# CellVoltageControl.net
KiCad netlist of a schematic drawn in Altium Designer
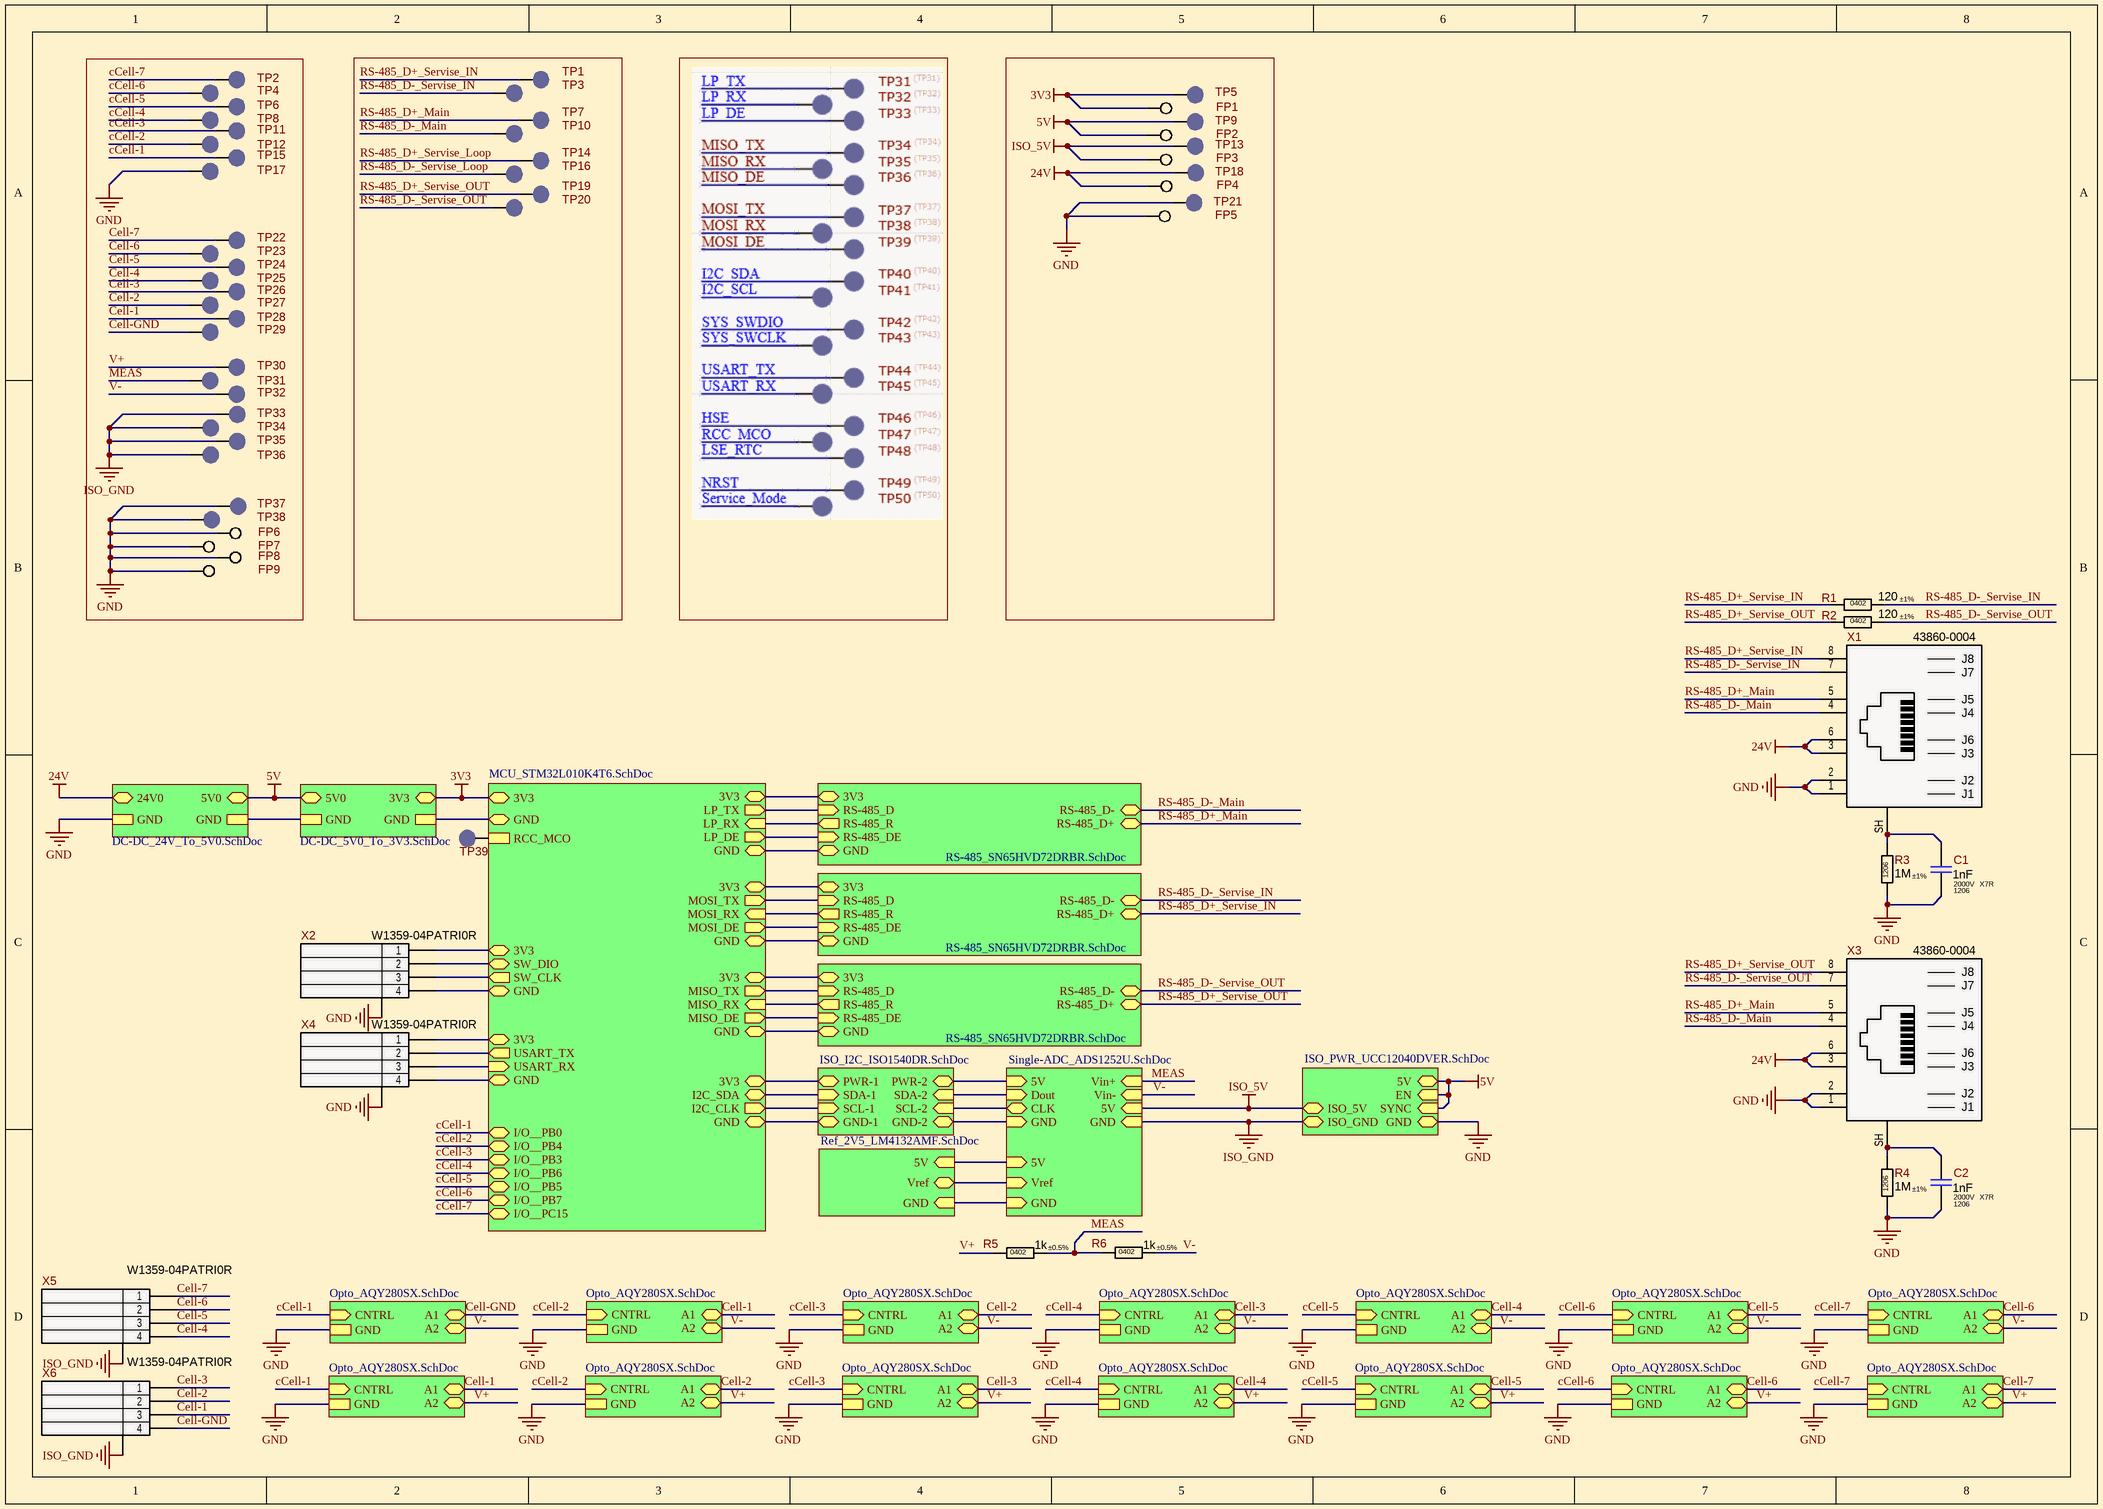
[diagram p0: CellVoltageControl.SchDoc]

(export (version "E")
  (design (tool "Eeschema 10.0.6"))
  (components
    (comp (ref "C1")
      (value "1nF")
      (footprint "CAP-1206(3216)X125T20")
      (description "1nF 2000V X7R ±10% 1206 Ceramic Capacitor RoHS")
      (fields
        (field (name "PACKAGE") "1206")
        (field (name "VOLTAGE") "2000V")
        (field (name "DIELECTRIC TYPE") "X7R")
        (field (name "PART NUMBER") "CC1206KKX7RDBB102")
        (field (name "MANUFACTURER") "Yageo")
      )
      (libsource (lib "EL.CVCM.T01") (part "Capacitor-NonPolar"))
    )
    (comp (ref "C2")
      (value "1nF")
      (footprint "CAP-1206(3216)X125T20")
      (description "1nF 2000V X7R ±10% 1206 Ceramic Capacitor RoHS")
      (fields
        (field (name "PACKAGE") "1206")
        (field (name "VOLTAGE") "2000V")
        (field (name "DIELECTRIC TYPE") "X7R")
        (field (name "PART NUMBER") "CC1206KKX7RDBB102")
        (field (name "MANUFACTURER") "Yageo")
      )
      (libsource (lib "EL.CVCM.T01") (part "Capacitor-NonPolar"))
    )
    (comp (ref "FP1")
      (value "PAD-1.1mm")
      (footprint "PAD-1.1mm")
      (description "1.1mm Pad for Plug-In or Receptacle")
      (fields (field (name "MANUFACTURER") "NONE"))
      (libsource (lib "EL.CVCM.T01") (part "Pad"))
    )
    (comp (ref "FP2")
      (value "PAD-1.1mm")
      (footprint "PAD-1.1mm")
      (description "1.1mm Pad for Plug-In or Receptacle")
      (fields (field (name "MANUFACTURER") "NONE"))
      (libsource (lib "EL.CVCM.T01") (part "Pad"))
    )
    (comp (ref "FP3")
      (value "PAD-1.1mm")
      (footprint "PAD-1.1mm")
      (description "1.1mm Pad for Plug-In or Receptacle")
      (fields (field (name "MANUFACTURER") "NONE"))
      (libsource (lib "EL.CVCM.T01") (part "Pad"))
    )
    (comp (ref "FP4")
      (value "PAD-1.1mm")
      (footprint "PAD-1.1mm")
      (description "1.1mm Pad for Plug-In or Receptacle")
      (fields (field (name "MANUFACTURER") "NONE"))
      (libsource (lib "EL.CVCM.T01") (part "Pad"))
    )
    (comp (ref "FP5")
      (value "PAD-1.1mm")
      (footprint "PAD-1.1mm")
      (description "1.1mm Pad for Plug-In or Receptacle")
      (fields (field (name "MANUFACTURER") "NONE"))
      (libsource (lib "EL.CVCM.T01") (part "Pad"))
    )
    (comp (ref "FP6")
      (value "PAD-1.1mm")
      (footprint "PAD-1.1mm")
      (description "1.1mm Pad for Plug-In or Receptacle")
      (fields (field (name "MANUFACTURER") "NONE"))
      (libsource (lib "EL.CVCM.T01") (part "Pad"))
    )
    (comp (ref "FP7")
      (value "PAD-1.1mm")
      (footprint "PAD-1.1mm")
      (description "1.1mm Pad for Plug-In or Receptacle")
      (fields (field (name "MANUFACTURER") "NONE"))
      (libsource (lib "EL.CVCM.T01") (part "Pad"))
    )
    (comp (ref "FP8")
      (value "PAD-1.1mm")
      (footprint "PAD-1.1mm")
      (description "1.1mm Pad for Plug-In or Receptacle")
      (fields (field (name "MANUFACTURER") "NONE"))
      (libsource (lib "EL.CVCM.T01") (part "Pad"))
    )
    (comp (ref "FP9")
      (value "PAD-1.1mm")
      (footprint "PAD-1.1mm")
      (description "1.1mm Pad for Plug-In or Receptacle")
      (fields (field (name "MANUFACTURER") "NONE"))
      (libsource (lib "EL.CVCM.T01") (part "Pad"))
    )
    (comp (ref "R1")
      (value "120")
      (footprint "R_ANY_CHIP_0402_HI")
      (description "120 Ohms ±1% 1/16W 0402 Thick Film Resistor")
      (fields
        (field (name "TOLERANCE") "±1%")
        (field (name "PACKAGE") "0402")
        (field (name "PART NUMBER") "RC0402FR-07120RL")
        (field (name "MANUFACTURER") "Yageo")
      )
      (libsource (lib "EL.CVCM.T01") (part "Resistor"))
    )
    (comp (ref "R2")
      (value "120")
      (footprint "R_ANY_CHIP_0402_HI")
      (description "120 Ohms ±1% 1/16W 0402 Thick Film Resistor")
      (fields
        (field (name "TOLERANCE") "±1%")
        (field (name "PACKAGE") "0402")
        (field (name "PART NUMBER") "RC0402FR-07120RL")
        (field (name "MANUFACTURER") "Yageo")
      )
      (libsource (lib "EL.CVCM.T01") (part "Resistor"))
    )
    (comp (ref "R3")
      (value "1M")
      (footprint "CHV1206-Series")
      (description "1 MOhms ±1%, 1/4W 1206 Thick Film Resistor")
      (fields
        (field (name "TOLERANCE") "±1%")
        (field (name "PACKAGE") "1206")
        (field (name "PART NUMBER") "CHV1206-FX-1004ELF")
        (field (name "MANUFACTURER") "Bourns")
      )
      (libsource (lib "EL.CVCM.T01") (part "Resistor"))
    )
    (comp (ref "R4")
      (value "1M")
      (footprint "CHV1206-Series")
      (description "1 MOhms ±1%, 1/4W 1206 Thick Film Resistor")
      (fields
        (field (name "TOLERANCE") "±1%")
        (field (name "PACKAGE") "1206")
        (field (name "PART NUMBER") "CHV1206-FX-1004ELF")
        (field (name "MANUFACTURER") "Bourns")
      )
      (libsource (lib "EL.CVCM.T01") (part "Resistor"))
    )
    (comp (ref "R5")
      (value "1k")
      (footprint "R_ANY_CHIP_0402_MED")
      (description "1 kOhms ±0.5% 1/16W 0402 Thick Film Resistor")
      (fields
        (field (name "TOLERANCE") "±0.5%")
        (field (name "PACKAGE") "0402")
        (field (name "PART NUMBER") "RC0402DR-071KL")
        (field (name "MANUFACTURER") "Yageo")
      )
      (libsource (lib "EL.CVCM.T01") (part "Resistor"))
    )
    (comp (ref "R6")
      (value "1k")
      (footprint "R_ANY_CHIP_0402_MED")
      (description "1 kOhms ±0.5% 1/16W 0402 Thick Film Resistor")
      (fields
        (field (name "TOLERANCE") "±0.5%")
        (field (name "PACKAGE") "0402")
        (field (name "PART NUMBER") "RC0402DR-071KL")
        (field (name "MANUFACTURER") "Yageo")
      )
      (libsource (lib "EL.CVCM.T01") (part "Resistor"))
    )
    (comp (ref "TP1")
      (value "LED_LINK")
      (footprint "TP_SMD_2mm")
      (description "Test Point SMD Pad 1.0mm/1.5mm/2mm")
      (fields (field (name "PART NUMBER") "TP-PAD-SMD"))
      (libsource (lib "EL.CVCM.T01") (part "Test-Point-SMD-1"))
    )
    (comp (ref "TP2")
      (value "LED_LINK")
      (footprint "TP_SMD_2mm")
      (description "Test Point SMD Pad 1.0mm/1.5mm/2mm")
      (fields (field (name "PART NUMBER") "TP-PAD-SMD"))
      (libsource (lib "EL.CVCM.T01") (part "Test-Point-SMD-1"))
    )
    (comp (ref "TP3")
      (value "LED_LINK")
      (footprint "TP_SMD_2mm")
      (description "Test Point SMD Pad 1.0mm/1.5mm/2mm")
      (fields (field (name "PART NUMBER") "TP-PAD-SMD"))
      (libsource (lib "EL.CVCM.T01") (part "Test-Point-SMD-1"))
    )
    (comp (ref "TP4")
      (value "LED_LINK")
      (footprint "TP_SMD_2mm")
      (description "Test Point SMD Pad 1.0mm/1.5mm/2mm")
      (fields (field (name "PART NUMBER") "TP-PAD-SMD"))
      (libsource (lib "EL.CVCM.T01") (part "Test-Point-SMD-1"))
    )
    (comp (ref "TP5")
      (value "LED_LINK")
      (footprint "TP_SMD_2mm")
      (description "Test Point SMD Pad 1.0mm/1.5mm/2mm")
      (fields (field (name "PART NUMBER") "TP-PAD-SMD"))
      (libsource (lib "EL.CVCM.T01") (part "Test-Point-SMD-1"))
    )
    (comp (ref "TP6")
      (value "LED_LINK")
      (footprint "TP_SMD_2mm")
      (description "Test Point SMD Pad 1.0mm/1.5mm/2mm")
      (fields (field (name "PART NUMBER") "TP-PAD-SMD"))
      (libsource (lib "EL.CVCM.T01") (part "Test-Point-SMD-1"))
    )
    (comp (ref "TP7")
      (value "LED_LINK")
      (footprint "TP_SMD_2mm")
      (description "Test Point SMD Pad 1.0mm/1.5mm/2mm")
      (fields (field (name "PART NUMBER") "TP-PAD-SMD"))
      (libsource (lib "EL.CVCM.T01") (part "Test-Point-SMD-1"))
    )
    (comp (ref "TP8")
      (value "LED_LINK")
      (footprint "TP_SMD_2mm")
      (description "Test Point SMD Pad 1.0mm/1.5mm/2mm")
      (fields (field (name "PART NUMBER") "TP-PAD-SMD"))
      (libsource (lib "EL.CVCM.T01") (part "Test-Point-SMD-1"))
    )
    (comp (ref "TP9")
      (value "LED_LINK")
      (footprint "TP_SMD_2mm")
      (description "Test Point SMD Pad 1.0mm/1.5mm/2mm")
      (fields (field (name "PART NUMBER") "TP-PAD-SMD"))
      (libsource (lib "EL.CVCM.T01") (part "Test-Point-SMD-1"))
    )
    (comp (ref "TP10")
      (value "LED_LINK")
      (footprint "TP_SMD_2mm")
      (description "Test Point SMD Pad 1.0mm/1.5mm/2mm")
      (fields (field (name "PART NUMBER") "TP-PAD-SMD"))
      (libsource (lib "EL.CVCM.T01") (part "Test-Point-SMD-1"))
    )
    (comp (ref "TP11")
      (value "LED_LINK")
      (footprint "TP_SMD_2mm")
      (description "Test Point SMD Pad 1.0mm/1.5mm/2mm")
      (fields (field (name "PART NUMBER") "TP-PAD-SMD"))
      (libsource (lib "EL.CVCM.T01") (part "Test-Point-SMD-1"))
    )
    (comp (ref "TP12")
      (value "LED_LINK")
      (footprint "TP_SMD_2mm")
      (description "Test Point SMD Pad 1.0mm/1.5mm/2mm")
      (fields (field (name "PART NUMBER") "TP-PAD-SMD"))
      (libsource (lib "EL.CVCM.T01") (part "Test-Point-SMD-1"))
    )
    (comp (ref "TP13")
      (value "LED_LINK")
      (footprint "TP_SMD_2mm")
      (description "Test Point SMD Pad 1.0mm/1.5mm/2mm")
      (fields (field (name "PART NUMBER") "TP-PAD-SMD"))
      (libsource (lib "EL.CVCM.T01") (part "Test-Point-SMD-1"))
    )
    (comp (ref "TP14")
      (value "LED_LINK")
      (footprint "TP_SMD_2mm")
      (description "Test Point SMD Pad 1.0mm/1.5mm/2mm")
      (fields (field (name "PART NUMBER") "TP-PAD-SMD"))
      (libsource (lib "EL.CVCM.T01") (part "Test-Point-SMD-1"))
    )
    (comp (ref "TP15")
      (value "LED_LINK")
      (footprint "TP_SMD_2mm")
      (description "Test Point SMD Pad 1.0mm/1.5mm/2mm")
      (fields (field (name "PART NUMBER") "TP-PAD-SMD"))
      (libsource (lib "EL.CVCM.T01") (part "Test-Point-SMD-1"))
    )
    (comp (ref "TP16")
      (value "LED_LINK")
      (footprint "TP_SMD_2mm")
      (description "Test Point SMD Pad 1.0mm/1.5mm/2mm")
      (fields (field (name "PART NUMBER") "TP-PAD-SMD"))
      (libsource (lib "EL.CVCM.T01") (part "Test-Point-SMD-1"))
    )
    (comp (ref "TP17")
      (value "LED_LINK")
      (footprint "TP_SMD_2mm")
      (description "Test Point SMD Pad 1.0mm/1.5mm/2mm")
      (fields (field (name "PART NUMBER") "TP-PAD-SMD"))
      (libsource (lib "EL.CVCM.T01") (part "Test-Point-SMD-1"))
    )
    (comp (ref "TP18")
      (value "LED_LINK")
      (footprint "TP_SMD_2mm")
      (description "Test Point SMD Pad 1.0mm/1.5mm/2mm")
      (fields (field (name "PART NUMBER") "TP-PAD-SMD"))
      (libsource (lib "EL.CVCM.T01") (part "Test-Point-SMD-1"))
    )
    (comp (ref "TP19")
      (value "LED_LINK")
      (footprint "TP_SMD_2mm")
      (description "Test Point SMD Pad 1.0mm/1.5mm/2mm")
      (fields (field (name "PART NUMBER") "TP-PAD-SMD"))
      (libsource (lib "EL.CVCM.T01") (part "Test-Point-SMD-1"))
    )
    (comp (ref "TP20")
      (value "LED_LINK")
      (footprint "TP_SMD_2mm")
      (description "Test Point SMD Pad 1.0mm/1.5mm/2mm")
      (fields (field (name "PART NUMBER") "TP-PAD-SMD"))
      (libsource (lib "EL.CVCM.T01") (part "Test-Point-SMD-1"))
    )
    (comp (ref "TP21")
      (value "LED_LINK")
      (footprint "TP_SMD_2mm")
      (description "Test Point SMD Pad 1.0mm/1.5mm/2mm")
      (fields (field (name "PART NUMBER") "TP-PAD-SMD"))
      (libsource (lib "EL.CVCM.T01") (part "Test-Point-SMD-1"))
    )
    (comp (ref "TP22")
      (value "LED_LINK")
      (footprint "TP_SMD_2mm")
      (description "Test Point SMD Pad 1.0mm/1.5mm/2mm")
      (fields (field (name "PART NUMBER") "TP-PAD-SMD"))
      (libsource (lib "EL.CVCM.T01") (part "Test-Point-SMD-1"))
    )
    (comp (ref "TP23")
      (value "LED_LINK")
      (footprint "TP_SMD_2mm")
      (description "Test Point SMD Pad 1.0mm/1.5mm/2mm")
      (fields (field (name "PART NUMBER") "TP-PAD-SMD"))
      (libsource (lib "EL.CVCM.T01") (part "Test-Point-SMD-1"))
    )
    (comp (ref "TP24")
      (value "LED_LINK")
      (footprint "TP_SMD_2mm")
      (description "Test Point SMD Pad 1.0mm/1.5mm/2mm")
      (fields (field (name "PART NUMBER") "TP-PAD-SMD"))
      (libsource (lib "EL.CVCM.T01") (part "Test-Point-SMD-1"))
    )
    (comp (ref "TP25")
      (value "LED_LINK")
      (footprint "TP_SMD_2mm")
      (description "Test Point SMD Pad 1.0mm/1.5mm/2mm")
      (fields (field (name "PART NUMBER") "TP-PAD-SMD"))
      (libsource (lib "EL.CVCM.T01") (part "Test-Point-SMD-1"))
    )
    (comp (ref "TP26")
      (value "LED_LINK")
      (footprint "TP_SMD_2mm")
      (description "Test Point SMD Pad 1.0mm/1.5mm/2mm")
      (fields (field (name "PART NUMBER") "TP-PAD-SMD"))
      (libsource (lib "EL.CVCM.T01") (part "Test-Point-SMD-1"))
    )
    (comp (ref "TP27")
      (value "LED_LINK")
      (footprint "TP_SMD_2mm")
      (description "Test Point SMD Pad 1.0mm/1.5mm/2mm")
      (fields (field (name "PART NUMBER") "TP-PAD-SMD"))
      (libsource (lib "EL.CVCM.T01") (part "Test-Point-SMD-1"))
    )
    (comp (ref "TP28")
      (value "LED_LINK")
      (footprint "TP_SMD_2mm")
      (description "Test Point SMD Pad 1.0mm/1.5mm/2mm")
      (fields (field (name "PART NUMBER") "TP-PAD-SMD"))
      (libsource (lib "EL.CVCM.T01") (part "Test-Point-SMD-1"))
    )
    (comp (ref "TP29")
      (value "LED_LINK")
      (footprint "TP_SMD_2mm")
      (description "Test Point SMD Pad 1.0mm/1.5mm/2mm")
      (fields (field (name "PART NUMBER") "TP-PAD-SMD"))
      (libsource (lib "EL.CVCM.T01") (part "Test-Point-SMD-1"))
    )
    (comp (ref "TP30")
      (value "LED_LINK")
      (footprint "TP_SMD_2mm")
      (description "Test Point SMD Pad 1.0mm/1.5mm/2mm")
      (fields (field (name "PART NUMBER") "TP-PAD-SMD"))
      (libsource (lib "EL.CVCM.T01") (part "Test-Point-SMD-1"))
    )
    (comp (ref "TP31")
      (value "LED_LINK")
      (footprint "TP_SMD_2mm")
      (description "Test Point SMD Pad 1.0mm/1.5mm/2mm")
      (fields (field (name "PART NUMBER") "TP-PAD-SMD"))
      (libsource (lib "EL.CVCM.T01") (part "Test-Point-SMD-1"))
    )
    (comp (ref "TP32")
      (value "LED_LINK")
      (footprint "TP_SMD_2mm")
      (description "Test Point SMD Pad 1.0mm/1.5mm/2mm")
      (fields (field (name "PART NUMBER") "TP-PAD-SMD"))
      (libsource (lib "EL.CVCM.T01") (part "Test-Point-SMD-1"))
    )
    (comp (ref "TP33")
      (value "LED_LINK")
      (footprint "TP_SMD_2mm")
      (description "Test Point SMD Pad 1.0mm/1.5mm/2mm")
      (fields (field (name "PART NUMBER") "TP-PAD-SMD"))
      (libsource (lib "EL.CVCM.T01") (part "Test-Point-SMD-1"))
    )
    (comp (ref "TP34")
      (value "LED_LINK")
      (footprint "TP_SMD_2mm")
      (description "Test Point SMD Pad 1.0mm/1.5mm/2mm")
      (fields (field (name "PART NUMBER") "TP-PAD-SMD"))
      (libsource (lib "EL.CVCM.T01") (part "Test-Point-SMD-1"))
    )
    (comp (ref "TP35")
      (value "LED_LINK")
      (footprint "TP_SMD_2mm")
      (description "Test Point SMD Pad 1.0mm/1.5mm/2mm")
      (fields (field (name "PART NUMBER") "TP-PAD-SMD"))
      (libsource (lib "EL.CVCM.T01") (part "Test-Point-SMD-1"))
    )
    (comp (ref "TP36")
      (value "LED_LINK")
      (footprint "TP_SMD_2mm")
      (description "Test Point SMD Pad 1.0mm/1.5mm/2mm")
      (fields (field (name "PART NUMBER") "TP-PAD-SMD"))
      (libsource (lib "EL.CVCM.T01") (part "Test-Point-SMD-1"))
    )
    (comp (ref "TP37")
      (value "LED_LINK")
      (footprint "TP_SMD_2mm")
      (description "Test Point SMD Pad 1.0mm/1.5mm/2mm")
      (fields (field (name "PART NUMBER") "TP-PAD-SMD"))
      (libsource (lib "EL.CVCM.T01") (part "Test-Point-SMD-1"))
    )
    (comp (ref "TP38")
      (value "LED_LINK")
      (footprint "TP_SMD_2mm")
      (description "Test Point SMD Pad 1.0mm/1.5mm/2mm")
      (fields (field (name "PART NUMBER") "TP-PAD-SMD"))
      (libsource (lib "EL.CVCM.T01") (part "Test-Point-SMD-1"))
    )
    (comp (ref "TP39")
      (value "LED_LINK")
      (footprint "TP_SMD_2mm")
      (description "Test Point SMD Pad 1.0mm/1.5mm/2mm")
      (fields (field (name "PART NUMBER") "TP-PAD-SMD"))
      (libsource (lib "EL.CVCM.T01") (part "Test-Point-SMD-1"))
    )
    (comp (ref "X1")
      (value "43860-0004")
      (footprint "43860-0004")
      (description "RJ45 8P8C Shielded Cat 3 10 Base-T Connector")
      (fields (field (name "PART NUMBER") "43860-0004") (field (name "MANUFACTURER") "Molex"))
      (libsource (lib "EL.CVCM.T01") (part "43860-0004"))
    )
    (comp (ref "X2")
      (value "W1359-04PATRI0R")
      (footprint "W1359-04PATXI0R_DBG")
      (description "1.25mm Wire-to-Board Header, Vertical, SMT, 4 pin")
      (fields
        (field (name "PART NUMBER") "W1359-04PATRI0R")
        (field (name "MANUFACTURER") "Hsuan Mao Technology")
      )
      (libsource (lib "EL.CVCM.T01") (part "General-4-Pin-MP"))
    )
    (comp (ref "X3")
      (value "43860-0004")
      (footprint "43860-0004")
      (description "RJ45 8P8C Shielded Cat 3 10 Base-T Connector")
      (fields (field (name "PART NUMBER") "43860-0004") (field (name "MANUFACTURER") "Molex"))
      (libsource (lib "EL.CVCM.T01") (part "43860-0004"))
    )
    (comp (ref "X4")
      (value "W1359-04PATRI0R")
      (footprint "W1359-04PATXI0R_DBG")
      (description "1.25mm Wire-to-Board Header, Vertical, SMT, 4 pin")
      (fields
        (field (name "PART NUMBER") "W1359-04PATRI0R")
        (field (name "MANUFACTURER") "Hsuan Mao Technology")
      )
      (libsource (lib "EL.CVCM.T01") (part "General-4-Pin-MP"))
    )
    (comp (ref "X5")
      (value "W1359-04PATRI0R")
      (footprint "W1359-04PATXI0R_DBG")
      (description "1.25mm Wire-to-Board Header, Vertical, SMT, 4 pin")
      (fields
        (field (name "PART NUMBER") "W1359-04PATRI0R")
        (field (name "MANUFACTURER") "Hsuan Mao Technology")
      )
      (libsource (lib "EL.CVCM.T01") (part "General-4-Pin-MP"))
    )
    (comp (ref "X6")
      (value "W1359-04PATRI0R")
      (footprint "W1359-04PATXI0R_DBG")
      (description "1.25mm Wire-to-Board Header, Vertical, SMT, 4 pin")
      (fields
        (field (name "PART NUMBER") "W1359-04PATRI0R")
        (field (name "MANUFACTURER") "Hsuan Mao Technology")
      )
      (libsource (lib "EL.CVCM.T01") (part "General-4-Pin-MP"))
    )
  )
  (nets
    (net (code "2") (name "/3V3_1") (class "Default")
      (node (ref "X4") (pin "1") (pinfunction "1_1") (pintype "passive"))
    )
    (net (code "3") (name "/3V3_2") (class "Default")
      (node (ref "X2") (pin "1") (pinfunction "1_1") (pintype "passive"))
    )
    (net (code "16") (name "/Cell-1") (class "Default")
      (node (ref "TP28") (pin "1") (pintype "passive"))
      (node (ref "X6") (pin "3") (pinfunction "3_3") (pintype "passive"))
    )
    (net (code "17") (name "/Cell-2") (class "Default")
      (node (ref "TP27") (pin "1") (pintype "passive"))
      (node (ref "X6") (pin "2") (pinfunction "2_2") (pintype "passive"))
    )
    (net (code "18") (name "/Cell-3") (class "Default")
      (node (ref "TP26") (pin "1") (pintype "passive"))
      (node (ref "X6") (pin "1") (pinfunction "1_1") (pintype "passive"))
    )
    (net (code "19") (name "/Cell-4") (class "Default")
      (node (ref "TP25") (pin "1") (pintype "passive"))
      (node (ref "X5") (pin "4") (pinfunction "4_4") (pintype "passive"))
    )
    (net (code "20") (name "/Cell-5") (class "Default")
      (node (ref "TP24") (pin "1") (pintype "passive"))
      (node (ref "X5") (pin "3") (pinfunction "3_3") (pintype "passive"))
    )
    (net (code "21") (name "/Cell-6") (class "Default")
      (node (ref "TP23") (pin "1") (pintype "passive"))
      (node (ref "X5") (pin "2") (pinfunction "2_2") (pintype "passive"))
    )
    (net (code "22") (name "/Cell-7") (class "Default")
      (node (ref "TP22") (pin "1") (pintype "passive"))
      (node (ref "X5") (pin "1") (pinfunction "1_1") (pintype "passive"))
    )
    (net (code "23") (name "/Cell-GND") (class "Default")
      (node (ref "TP29") (pin "1") (pintype "passive"))
      (node (ref "X6") (pin "4") (pinfunction "4_4") (pintype "passive"))
    )
    (net (code "26") (name "/GND_1") (class "Default")
      (node (ref "X4") (pin "4") (pinfunction "4_4") (pintype "passive"))
    )
    (net (code "27") (name "/GND_2") (class "Default")
      (node (ref "X2") (pin "4") (pinfunction "4_4") (pintype "passive"))
    )
    (net (code "44") (name "/MEAS") (class "Default")
      (node (ref "R5") (pin "2") (pintype "passive"))
      (node (ref "R6") (pin "1") (pintype "passive"))
      (node (ref "TP31") (pin "1") (pintype "passive"))
    )
    (net (code "51") (name "/RCC_MCO") (class "Default") (node (ref "TP39") (pin "1") (pintype "passive")))
    (net (code "53") (name "/RS-485_D+_Main") (class "Default")
      (node (ref "TP7") (pin "1") (pintype "passive"))
      (node (ref "X1") (pin "5") (pinfunction "CT_5") (pintype "passive"))
      (node (ref "X3") (pin "5") (pinfunction "CT_5") (pintype "passive"))
    )
    (net (code "54") (name "/RS-485_D+_Servise_IN") (class "Default")
      (node (ref "R1") (pin "1") (pintype "passive"))
      (node (ref "TP1") (pin "1") (pintype "passive"))
      (node (ref "X1") (pin "8") (pinfunction "TD2+_8") (pintype "passive"))
    )
    (net (code "55") (name "/RS-485_D+_Servise_Loop") (class "Default")
      (node (ref "TP14") (pin "1") (pintype "passive"))
    )
    (net (code "56") (name "/RS-485_D+_Servise_OUT") (class "Default")
      (node (ref "R2") (pin "1") (pintype "passive"))
      (node (ref "TP19") (pin "1") (pintype "passive"))
      (node (ref "X3") (pin "8") (pinfunction "TD2+_8") (pintype "passive"))
    )
    (net (code "57") (name "/RS-485_D-_Main") (class "Default")
      (node (ref "TP10") (pin "1") (pintype "passive"))
      (node (ref "X1") (pin "4") (pinfunction "TD3+_4") (pintype "passive"))
      (node (ref "X3") (pin "4") (pinfunction "TD3+_4") (pintype "passive"))
    )
    (net (code "58") (name "/RS-485_D-_Servise_IN") (class "Default")
      (node (ref "R1") (pin "2") (pintype "passive"))
      (node (ref "TP3") (pin "1") (pintype "passive"))
      (node (ref "X1") (pin "7") (pinfunction "TD2-_7") (pintype "passive"))
    )
    (net (code "59") (name "/RS-485_D-_Servise_Loop") (class "Default")
      (node (ref "TP16") (pin "1") (pintype "passive"))
    )
    (net (code "60") (name "/RS-485_D-_Servise_OUT") (class "Default")
      (node (ref "R2") (pin "2") (pintype "passive"))
      (node (ref "TP20") (pin "1") (pintype "passive"))
      (node (ref "X3") (pin "7") (pinfunction "TD2-_7") (pintype "passive"))
    )
    (net (code "69") (name "/SW_CLK") (class "Default")
      (node (ref "X2") (pin "3") (pinfunction "3_3") (pintype "passive"))
    )
    (net (code "70") (name "/SW_DIO") (class "Default")
      (node (ref "X2") (pin "2") (pinfunction "2_2") (pintype "passive"))
    )
    (net (code "71") (name "/USART_RX") (class "Default")
      (node (ref "X4") (pin "3") (pinfunction "3_3") (pintype "passive"))
    )
    (net (code "72") (name "/USART_TX") (class "Default")
      (node (ref "X4") (pin "2") (pinfunction "2_2") (pintype "passive"))
    )
    (net (code "73") (name "/V+") (class "Default")
      (node (ref "R5") (pin "1") (pintype "passive"))
      (node (ref "TP30") (pin "1") (pintype "passive"))
    )
    (net (code "74") (name "/V-") (class "Default")
      (node (ref "R6") (pin "2") (pintype "passive"))
      (node (ref "TP32") (pin "1") (pintype "passive"))
    )
    (net (code "76") (name "/cCell-1") (class "Default") (node (ref "TP15") (pin "1") (pintype "passive")))
    (net (code "77") (name "/cCell-2") (class "Default") (node (ref "TP12") (pin "1") (pintype "passive")))
    (net (code "78") (name "/cCell-3") (class "Default") (node (ref "TP11") (pin "1") (pintype "passive")))
    (net (code "79") (name "/cCell-4") (class "Default") (node (ref "TP8") (pin "1") (pintype "passive")))
    (net (code "80") (name "/cCell-5") (class "Default") (node (ref "TP6") (pin "1") (pintype "passive")))
    (net (code "81") (name "/cCell-6") (class "Default") (node (ref "TP4") (pin "1") (pintype "passive")))
    (net (code "82") (name "/cCell-7") (class "Default") (node (ref "TP2") (pin "1") (pintype "passive")))
    (net (code "83") (name "3V3") (class "Default")
      (node (ref "FP1") (pin "1") (pintype "passive"))
      (node (ref "TP5") (pin "1") (pintype "passive"))
    )
    (net (code "84") (name "5V") (class "Default")
      (node (ref "FP2") (pin "1") (pintype "passive"))
      (node (ref "TP9") (pin "1") (pintype "passive"))
    )
    (net (code "85") (name "24V") (class "Default")
      (node (ref "FP4") (pin "1") (pintype "passive"))
      (node (ref "TP18") (pin "1") (pintype "passive"))
      (node (ref "X1") (pin "3") (pinfunction "TD3-_3") (pintype "passive"))
      (node (ref "X1") (pin "6") (pinfunction "CT_6") (pintype "passive"))
      (node (ref "X3") (pin "3") (pinfunction "TD3-_3") (pintype "passive"))
      (node (ref "X3") (pin "6") (pinfunction "CT_6") (pintype "passive"))
    )
    (net (code "86") (name "GND") (class "Default")
      (node (ref "C1") (pin "2") (pinfunction "2_2") (pintype "passive"))
      (node (ref "C2") (pin "2") (pinfunction "2_2") (pintype "passive"))
      (node (ref "FP5") (pin "1") (pintype "passive"))
      (node (ref "FP6") (pin "1") (pintype "passive"))
      (node (ref "FP7") (pin "1") (pintype "passive"))
      (node (ref "FP8") (pin "1") (pintype "passive"))
      (node (ref "FP9") (pin "1") (pintype "passive"))
      (node (ref "R3") (pin "2") (pintype "passive"))
      (node (ref "R4") (pin "2") (pintype "passive"))
      (node (ref "TP17") (pin "1") (pintype "passive"))
      (node (ref "TP21") (pin "1") (pintype "passive"))
      (node (ref "TP37") (pin "1") (pintype "passive"))
      (node (ref "TP38") (pin "1") (pintype "passive"))
      (node (ref "X1") (pin "1") (pinfunction "TD4-_1") (pintype "passive"))
      (node (ref "X1") (pin "2") (pinfunction "TD4+_2") (pintype "passive"))
      (node (ref "X2") (pin "MP") (pinfunction "MountPad_MP") (pintype "passive"))
      (node (ref "X3") (pin "1") (pinfunction "TD4-_1") (pintype "passive"))
      (node (ref "X3") (pin "2") (pinfunction "TD4+_2") (pintype "passive"))
      (node (ref "X4") (pin "MP") (pinfunction "MountPad_MP") (pintype "passive"))
    )
    (net (code "87") (name "ISO_5V") (class "Default")
      (node (ref "FP3") (pin "1") (pintype "passive"))
      (node (ref "TP13") (pin "1") (pintype "passive"))
    )
    (net (code "88") (name "ISO_GND") (class "Default")
      (node (ref "TP33") (pin "1") (pintype "passive"))
      (node (ref "TP34") (pin "1") (pintype "passive"))
      (node (ref "TP35") (pin "1") (pintype "passive"))
      (node (ref "TP36") (pin "1") (pintype "passive"))
      (node (ref "X5") (pin "MP") (pinfunction "MountPad_MP") (pintype "passive"))
      (node (ref "X6") (pin "MP") (pinfunction "MountPad_MP") (pintype "passive"))
    )
    (net (code "89") (name "Net-(X1-Shield)") (class "Default")
      (node (ref "C1") (pin "1") (pinfunction "1_1") (pintype "passive"))
      (node (ref "R3") (pin "1") (pintype "passive"))
      (node (ref "X1") (pin "SH") (pinfunction "Shield_SH") (pintype "passive"))
    )
    (net (code "90") (name "Net-(X3-Shield)") (class "Default")
      (node (ref "C2") (pin "1") (pinfunction "1_1") (pintype "passive"))
      (node (ref "R4") (pin "1") (pintype "passive"))
      (node (ref "X3") (pin "SH") (pinfunction "Shield_SH") (pintype "passive"))
    )
  )
)
